# Input_AC.net
KiCad netlist of a schematic drawn in Altium Designer
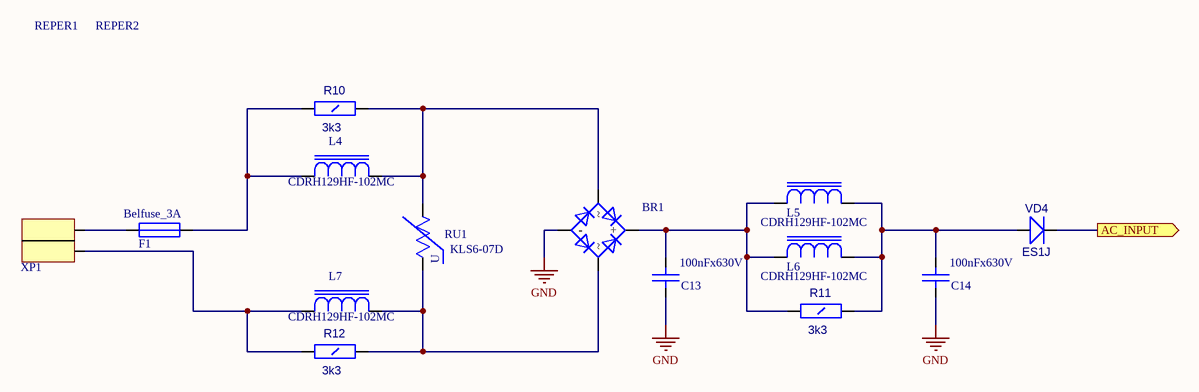
[diagram p0: Input_AC.SchDoc]

(export (version "E")
  (design (tool "Eeschema 10.0.6"))
  (components
    (comp (ref "BR1") (value "DF10S") (footprint "SDIP") (libsource (lib "gprs_modem_2") (part "DF10S")))
    (comp (ref "C13")
      (value "100nFx630V")
      (footprint "CAP_630V_SMD")
      (libsource (lib "gprs_modem_2") (part "Cap_HV"))
    )
    (comp (ref "C14")
      (value "100nFx630V")
      (footprint "CAP_630V_SMD")
      (libsource (lib "gprs_modem_2") (part "Cap_HV"))
    )
    (comp (ref "F1")
      (value "Belfuse_3A")
      (footprint "Fuse Belfuse")
      (libsource (lib "gprs_modem_2") (part "Fuse Belufse"))
    )
    (comp (ref "L4")
      (value "CDRH129HF-102MC")
      (footprint "IND_CDRH129")
      (libsource (lib "gprs_modem_2") (part "CDRH129"))
    )
    (comp (ref "L5")
      (value "CDRH129HF-102MC")
      (footprint "IND_CDRH129")
      (libsource (lib "gprs_modem_2") (part "CDRH129"))
    )
    (comp (ref "L6")
      (value "CDRH129HF-102MC")
      (footprint "IND_CDRH129")
      (libsource (lib "gprs_modem_2") (part "CDRH129"))
    )
    (comp (ref "L7")
      (value "CDRH129HF-102MC")
      (footprint "IND_CDRH129")
      (libsource (lib "gprs_modem_2") (part "CDRH129"))
    )
    (comp (ref "R10")
      (value "3k3")
      (footprint "RC1206")
      (description "RC1206")
      (libsource (lib "gprs_modem_2") (part "RC1206"))
    )
    (comp (ref "R11")
      (value "3k3")
      (footprint "RC1206")
      (description "RC1206")
      (libsource (lib "gprs_modem_2") (part "RC1206"))
    )
    (comp (ref "R12")
      (value "3k3")
      (footprint "RC1206")
      (description "RC1206")
      (libsource (lib "gprs_modem_2") (part "RC1206"))
    )
    (comp (ref "REPER1")
      (value "REPER1.2")
      (footprint "REPER1.2")
      (libsource (lib "gprs_modem") (part "REPER1.2"))
    )
    (comp (ref "REPER2")
      (value "REPER1.2")
      (footprint "REPER1.2")
      (libsource (lib "gprs_modem") (part "REPER1.2"))
    )
    (comp (ref "RU1")
      (value "KLS6-07D")
      (footprint "Varistor_7mm_SMD")
      (libsource (lib "gprs_modem_2") (part "KLS6-07D"))
    )
    (comp (ref "VD4")
      (value "ES1J")
      (footprint "SMA")
      (description "Schottky Rectifier")
      (libsource (lib "gprs_modem_2") (part "SS14"))
    )
    (comp (ref "XP1")
      (value "*")
      (footprint "Poke-In 2pin")
      (libsource (lib "gprs_modem_2") (part "Poke-IN 2Pin"))
    )
  )
  (nets
    (net (code "1") (name "/AC_INPUT") (class "Default")
      (node (ref "VD4") (pin "2") (pinfunction "K_2") (pintype "passive"))
    )
    (net (code "2") (name "GND") (class "Default")
      (node (ref "BR1") (pin "2") (pinfunction "-_2") (pintype "passive"))
      (node (ref "C13") (pin "1") (pinfunction "A_1") (pintype "passive"))
      (node (ref "C14") (pin "1") (pinfunction "A_1") (pintype "passive"))
    )
    (net (code "3") (name "Net-(BR1-+)") (class "Default")
      (node (ref "BR1") (pin "1") (pinfunction "+_1") (pintype "passive"))
      (node (ref "C13") (pin "2") (pinfunction "B_2") (pintype "passive"))
      (node (ref "L5") (pin "1") (pinfunction "A_1") (pintype "passive"))
      (node (ref "L6") (pin "1") (pinfunction "A_1") (pintype "passive"))
      (node (ref "R11") (pin "1") (pinfunction "A_1") (pintype "passive"))
    )
    (net (code "4") (name "Net-(C14-B)") (class "Default")
      (node (ref "C14") (pin "2") (pinfunction "B_2") (pintype "passive"))
      (node (ref "L5") (pin "2") (pinfunction "B_2") (pintype "passive"))
      (node (ref "L6") (pin "2") (pinfunction "B_2") (pintype "passive"))
      (node (ref "R11") (pin "2") (pinfunction "B_2") (pintype "passive"))
      (node (ref "VD4") (pin "1") (pinfunction "A_1") (pintype "passive"))
    )
    (net (code "5") (name "Net-(L4-A)") (class "Default")
      (node (ref "F1") (pin "1") (pintype "passive"))
      (node (ref "L4") (pin "1") (pinfunction "A_1") (pintype "passive"))
      (node (ref "R10") (pin "1") (pinfunction "A_1") (pintype "passive"))
    )
    (net (code "6") (name "Net-(L4-B)") (class "Default")
      (node (ref "BR1") (pin "3") (pinfunction "~_3") (pintype "passive"))
      (node (ref "L4") (pin "2") (pinfunction "B_2") (pintype "passive"))
      (node (ref "R10") (pin "2") (pinfunction "B_2") (pintype "passive"))
      (node (ref "RU1") (pin "2") (pinfunction "B_2") (pintype "passive"))
    )
    (net (code "7") (name "Net-(L7-A)") (class "Default")
      (node (ref "L7") (pin "1") (pinfunction "A_1") (pintype "passive"))
      (node (ref "R12") (pin "1") (pinfunction "A_1") (pintype "passive"))
      (node (ref "XP1") (pin "4") (pinfunction "10_4") (pintype "passive"))
    )
    (net (code "8") (name "Net-(L7-B)") (class "Default")
      (node (ref "BR1") (pin "4") (pinfunction "~_4") (pintype "passive"))
      (node (ref "L7") (pin "2") (pinfunction "B_2") (pintype "passive"))
      (node (ref "R12") (pin "2") (pinfunction "B_2") (pintype "passive"))
      (node (ref "RU1") (pin "1") (pinfunction "A_1") (pintype "passive"))
    )
    (net (code "9") (name "Net-(XP1-9)") (class "Default")
      (node (ref "F1") (pin "2") (pintype "passive"))
      (node (ref "XP1") (pin "3") (pinfunction "9_3") (pintype "passive"))
    )
    (net (code "10") (name "unconnected-(REPER1-Pad1)") (class "Default")
      (node (ref "REPER1") (pin "1") (pintype "passive"))
    )
    (net (code "11") (name "unconnected-(REPER2-Pad1)") (class "Default")
      (node (ref "REPER2") (pin "1") (pintype "passive"))
    )
  )
)
